# weblight_developer.net
KiCad netlist of a schematic drawn in EAGLE
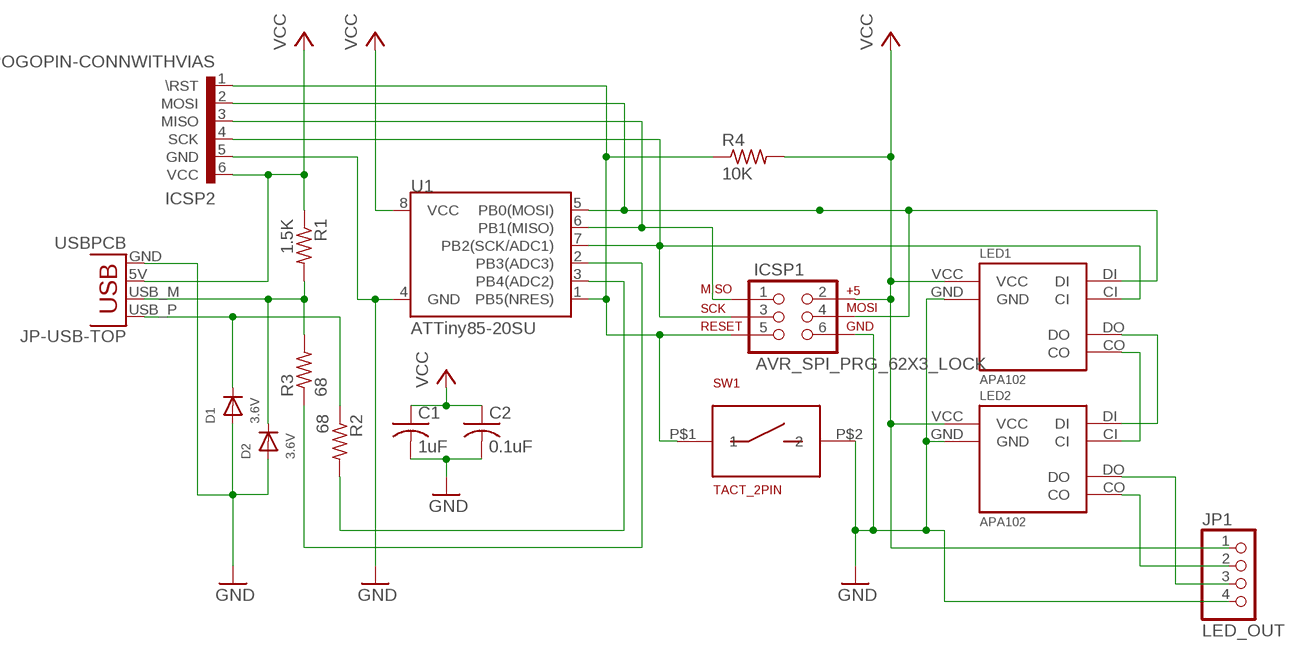
[diagram p0: schematic, sheet 1]

(export (version "E")
  (design (tool "Eeschema 10.0.6"))
  (components
    (comp (ref "C1")
      (value "1uF")
      (footprint "eagle-import:C0805")
      (libsource (lib "eagle-import") (part "C-USC0805"))
    )
    (comp (ref "C2")
      (value "0.1uF")
      (footprint "eagle-import:C0805")
      (libsource (lib "eagle-import") (part "C-USC0805"))
    )
    (comp (ref "D1")
      (value "3.6V")
      (footprint "eagle-import:SOD-323")
      (libsource (lib "eagle-import") (part "DIODESOD-323"))
    )
    (comp (ref "D2")
      (value "3.6V")
      (footprint "eagle-import:SOD-323")
      (libsource (lib "eagle-import") (part "DIODESOD-323"))
    )
    (comp (ref "ICSP1")
      (value "AVR_SPI_PRG_62X3_LOCK")
      (footprint "eagle-import:2X3_LOCK")
      (libsource (lib "eagle-import") (part "AVR_SPI_PRG_62X3_LOCK"))
    )
    (comp (ref "ICSP2")
      (value "POGOPIN-CONNWITHVIAS")
      (footprint "eagle-import:POGOPROG-CONN-0H")
      (libsource (lib "eagle-import") (part "POGOPIN-CONNWITHVIAS"))
    )
    (comp (ref "JP-USB-TOP")
      (value "USBPCB")
      (footprint "eagle-import:USB-A-PCB")
      (libsource (lib "eagle-import") (part "USBPCB"))
    )
    (comp (ref "JP1")
      (value "LED_OUT")
      (footprint "eagle-import:1X04_ROUND")
      (libsource (lib "eagle-import") (part "HEADER-1X4ROUND"))
    )
    (comp (ref "LED1")
      (value "APA102")
      (footprint "eagle-import:APA102")
      (libsource (lib "eagle-import") (part "APA102"))
    )
    (comp (ref "LED2")
      (value "APA102")
      (footprint "eagle-import:APA102")
      (libsource (lib "eagle-import") (part "APA102"))
    )
    (comp (ref "R1")
      (value "1.5K")
      (footprint "eagle-import:R0805")
      (libsource (lib "eagle-import") (part "R-US_R0805"))
    )
    (comp (ref "R2")
      (value "68")
      (footprint "eagle-import:R0805")
      (libsource (lib "eagle-import") (part "R-US_R0805"))
    )
    (comp (ref "R3")
      (value "68")
      (footprint "eagle-import:R0805")
      (libsource (lib "eagle-import") (part "R-US_R0805"))
    )
    (comp (ref "R4")
      (value "10K")
      (footprint "eagle-import:R0805")
      (libsource (lib "eagle-import") (part "R-US_R0805"))
    )
    (comp (ref "SW1")
      (value "TACT_2PIN")
      (footprint "eagle-import:TD-85XU")
      (libsource (lib "eagle-import") (part "TACT_2PIN"))
    )
    (comp (ref "U1")
      (value "ATTiny85-20SU")
      (footprint "eagle-import:SO08-EIAJ")
      (libsource (lib "eagle-import") (part "ATTINY45TINY85-20-SMT"))
    )
  )
  (nets
    (net (code "1") (name "GND") (class "Default")
      (node (ref "C1") (pin "2") (pinfunction "2_2") (pintype "passive"))
      (node (ref "C2") (pin "2") (pinfunction "2_2") (pintype "passive"))
      (node (ref "D1") (pin "A") (pinfunction "A_A") (pintype "passive"))
      (node (ref "D2") (pin "A") (pinfunction "A_A") (pintype "passive"))
      (node (ref "ICSP1") (pin "6") (pinfunction "6_6") (pintype "passive"))
      (node (ref "ICSP2") (pin "5") (pinfunction "GND_5") (pintype "bidirectional"))
      (node (ref "JP-USB-TOP") (pin "GND") (pinfunction "GND_GND") (pintype "bidirectional"))
      (node (ref "JP1") (pin "4") (pinfunction "4_4") (pintype "passive"))
      (node (ref "LED1") (pin "GND") (pinfunction "GND_GND") (pintype "power_in"))
      (node (ref "LED2") (pin "GND") (pinfunction "GND_GND") (pintype "power_in"))
      (node (ref "SW1") (pin "P$2") (pinfunction "2_P$2") (pintype "bidirectional"))
      (node (ref "U1") (pin "4") (pinfunction "GND_4") (pintype "bidirectional"))
    )
    (net (code "2") (name "Net-(ICSP2-MISO)") (class "Default")
      (node (ref "ICSP1") (pin "1") (pinfunction "1_1") (pintype "passive"))
      (node (ref "ICSP2") (pin "3") (pinfunction "MISO_3") (pintype "bidirectional"))
      (node (ref "U1") (pin "6") (pinfunction "PB1(MISO)_6") (pintype "bidirectional"))
    )
    (net (code "3") (name "Net-(ICSP2-MOSI)") (class "Default")
      (node (ref "ICSP1") (pin "4") (pinfunction "4_4") (pintype "passive"))
      (node (ref "ICSP2") (pin "2") (pinfunction "MOSI_2") (pintype "bidirectional"))
      (node (ref "LED1") (pin "DI") (pinfunction "DI_DI") (pintype "input"))
      (node (ref "U1") (pin "5") (pinfunction "PB0(MOSI)_5") (pintype "bidirectional"))
    )
    (net (code "4") (name "Net-(ICSP2-SCK)") (class "Default")
      (node (ref "ICSP1") (pin "3") (pinfunction "3_3") (pintype "passive"))
      (node (ref "ICSP2") (pin "4") (pinfunction "SCK_4") (pintype "bidirectional"))
      (node (ref "LED1") (pin "CI") (pinfunction "CI_CI") (pintype "input"))
      (node (ref "U1") (pin "7") (pinfunction "PB2(SCK/ADC1)_7") (pintype "bidirectional"))
    )
    (net (code "5") (name "Net-(ICSP2-\\RST)") (class "Default")
      (node (ref "ICSP1") (pin "5") (pinfunction "5_5") (pintype "passive"))
      (node (ref "ICSP2") (pin "1") (pinfunction "\\RST_1") (pintype "bidirectional"))
      (node (ref "R4") (pin "1") (pinfunction "1_1") (pintype "passive"))
      (node (ref "SW1") (pin "P$1") (pinfunction "1_P$1") (pintype "bidirectional"))
      (node (ref "U1") (pin "1") (pinfunction "PB5(NRES)_1") (pintype "bidirectional"))
    )
    (net (code "6") (name "Net-(JP-USB-TOP-D+)") (class "Default")
      (node (ref "D1") (pin "C") (pinfunction "C_C") (pintype "passive"))
      (node (ref "JP-USB-TOP") (pin "USB_P") (pinfunction "D+_USB_P") (pintype "bidirectional"))
      (node (ref "R2") (pin "1") (pinfunction "1_1") (pintype "passive"))
    )
    (net (code "7") (name "Net-(JP-USB-TOP-D-)") (class "Default")
      (node (ref "D2") (pin "C") (pinfunction "C_C") (pintype "passive"))
      (node (ref "JP-USB-TOP") (pin "USB_M") (pinfunction "D-_USB_M") (pintype "bidirectional"))
      (node (ref "R1") (pin "2") (pinfunction "2_2") (pintype "passive"))
      (node (ref "R3") (pin "2") (pinfunction "2_2") (pintype "passive"))
    )
    (net (code "8") (name "Net-(JP1-Pad2)") (class "Default")
      (node (ref "JP1") (pin "2") (pinfunction "2_2") (pintype "passive"))
      (node (ref "LED2") (pin "CO") (pinfunction "CO_CO") (pintype "output"))
    )
    (net (code "9") (name "Net-(JP1-Pad3)") (class "Default")
      (node (ref "JP1") (pin "3") (pinfunction "3_3") (pintype "passive"))
      (node (ref "LED2") (pin "DO") (pinfunction "DO_DO") (pintype "output"))
    )
    (net (code "10") (name "Net-(LED1-PadCO)") (class "Default")
      (node (ref "LED1") (pin "CO") (pinfunction "CO_CO") (pintype "output"))
      (node (ref "LED2") (pin "CI") (pinfunction "CI_CI") (pintype "input"))
    )
    (net (code "11") (name "Net-(LED1-PadDO)") (class "Default")
      (node (ref "LED1") (pin "DO") (pinfunction "DO_DO") (pintype "output"))
      (node (ref "LED2") (pin "DI") (pinfunction "DI_DI") (pintype "input"))
    )
    (net (code "12") (name "Net-(U1-PB3(ADC3))") (class "Default")
      (node (ref "R3") (pin "1") (pinfunction "1_1") (pintype "passive"))
      (node (ref "U1") (pin "2") (pinfunction "PB3(ADC3)_2") (pintype "bidirectional"))
    )
    (net (code "13") (name "Net-(U1-PB4(ADC2))") (class "Default")
      (node (ref "R2") (pin "2") (pinfunction "2_2") (pintype "passive"))
      (node (ref "U1") (pin "3") (pinfunction "PB4(ADC2)_3") (pintype "bidirectional"))
    )
    (net (code "14") (name "VCC") (class "Default")
      (node (ref "C1") (pin "1") (pinfunction "1_1") (pintype "passive"))
      (node (ref "C2") (pin "1") (pinfunction "1_1") (pintype "passive"))
      (node (ref "ICSP1") (pin "2") (pinfunction "2_2") (pintype "passive"))
      (node (ref "ICSP2") (pin "6") (pinfunction "VCC_6") (pintype "bidirectional"))
      (node (ref "JP-USB-TOP") (pin "5V") (pinfunction "VBUS_5V") (pintype "bidirectional"))
      (node (ref "JP1") (pin "1") (pinfunction "1_1") (pintype "passive"))
      (node (ref "LED1") (pin "VCC") (pinfunction "VCC_VCC") (pintype "power_in"))
      (node (ref "LED2") (pin "VCC") (pinfunction "VCC_VCC") (pintype "power_in"))
      (node (ref "R1") (pin "1") (pinfunction "1_1") (pintype "passive"))
      (node (ref "R4") (pin "2") (pinfunction "2_2") (pintype "passive"))
      (node (ref "U1") (pin "8") (pinfunction "VCC_8") (pintype "bidirectional"))
    )
  )
)
